# LitosConnector.net
KiCad netlist of a schematic drawn in Altium Designer
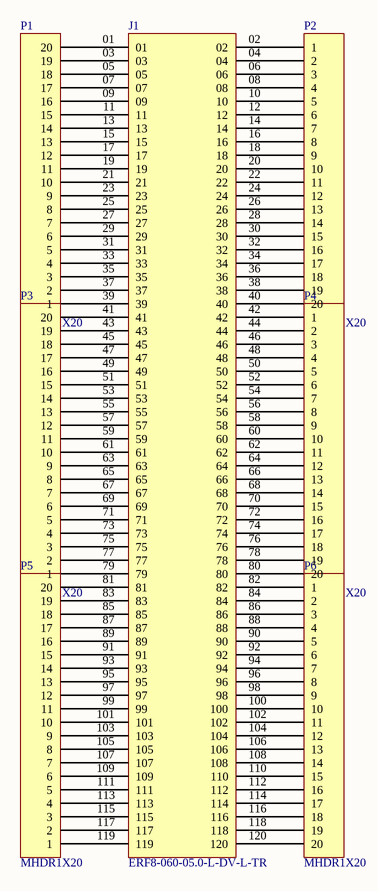
[diagram p0: LitosConnector.SchDoc]

(export (version "E")
  (design (tool "Eeschema 10.0.6"))
  (components
    (comp (ref "J1")
      (value "ERF8-060-05.0-L-DV-L-TR")
      (footprint "SAMTEC_ERF8-060-05.0-L-DV-L-TR")
      (libsource (lib "ERF8-060-05.0-L-DV-L-TR") (part "ERF8-060-05.0-L-DV-L-TR"))
    )
    (comp (ref "P1")
      (value "MHDR1X20")
      (footprint "MHDR1X20")
      (description "Header, 20-Pin")
      (fields (field (name "PUBLISHER") "Altium Limited"))
      (libsource (lib "") (part "MHDR1X20_1"))
    )
    (comp (ref "P2")
      (value "MHDR1X20")
      (footprint "MHDR1X20")
      (description "Header, 20-Pin")
      (fields (field (name "PUBLISHER") "Altium Limited"))
      (libsource (lib "Miscellaneous Connectors") (part "MHDR1X20"))
    )
    (comp (ref "P3")
      (value "MHDR1X20")
      (footprint "MHDR1X20")
      (description "Header, 20-Pin")
      (fields (field (name "PUBLISHER") "Altium Limited"))
      (libsource (lib "") (part "MHDR1X20_1"))
    )
    (comp (ref "P4")
      (value "MHDR1X20")
      (footprint "MHDR1X20")
      (description "Header, 20-Pin")
      (fields (field (name "PUBLISHER") "Altium Limited"))
      (libsource (lib "Miscellaneous Connectors") (part "MHDR1X20"))
    )
    (comp (ref "P5")
      (value "MHDR1X20")
      (footprint "MHDR1X20")
      (description "Header, 20-Pin")
      (fields (field (name "PUBLISHER") "Altium Limited"))
      (libsource (lib "") (part "MHDR1X20_1"))
    )
    (comp (ref "P6")
      (value "MHDR1X20")
      (footprint "MHDR1X20")
      (description "Header, 20-Pin")
      (fields (field (name "PUBLISHER") "Altium Limited"))
      (libsource (lib "Miscellaneous Connectors") (part "MHDR1X20"))
    )
  )
  (nets
    (net (code "1") (name "Net-(J1-Pad01)") (class "Default")
      (node (ref "J1") (pin "01") (pinfunction "01_01") (pintype "passive"))
      (node (ref "P1") (pin "20") (pinfunction "20_20") (pintype "passive"))
    )
    (net (code "2") (name "Net-(J1-Pad02)") (class "Default")
      (node (ref "J1") (pin "02") (pinfunction "02_02") (pintype "passive"))
      (node (ref "P2") (pin "1") (pinfunction "1_1") (pintype "passive"))
    )
    (net (code "3") (name "Net-(J1-Pad03)") (class "Default")
      (node (ref "J1") (pin "03") (pinfunction "03_03") (pintype "passive"))
      (node (ref "P1") (pin "19") (pinfunction "19_19") (pintype "passive"))
    )
    (net (code "4") (name "Net-(J1-Pad04)") (class "Default")
      (node (ref "J1") (pin "04") (pinfunction "04_04") (pintype "passive"))
      (node (ref "P2") (pin "2") (pinfunction "2_2") (pintype "passive"))
    )
    (net (code "5") (name "Net-(J1-Pad05)") (class "Default")
      (node (ref "J1") (pin "05") (pinfunction "05_05") (pintype "passive"))
      (node (ref "P1") (pin "18") (pinfunction "18_18") (pintype "passive"))
    )
    (net (code "6") (name "Net-(J1-Pad06)") (class "Default")
      (node (ref "J1") (pin "06") (pinfunction "06_06") (pintype "passive"))
      (node (ref "P2") (pin "3") (pinfunction "3_3") (pintype "passive"))
    )
    (net (code "7") (name "Net-(J1-Pad07)") (class "Default")
      (node (ref "J1") (pin "07") (pinfunction "07_07") (pintype "passive"))
      (node (ref "P1") (pin "17") (pinfunction "17_17") (pintype "passive"))
    )
    (net (code "8") (name "Net-(J1-Pad08)") (class "Default")
      (node (ref "J1") (pin "08") (pinfunction "08_08") (pintype "passive"))
      (node (ref "P2") (pin "4") (pinfunction "4_4") (pintype "passive"))
    )
    (net (code "9") (name "Net-(J1-Pad09)") (class "Default")
      (node (ref "J1") (pin "09") (pinfunction "09_09") (pintype "passive"))
      (node (ref "P1") (pin "16") (pinfunction "16_16") (pintype "passive"))
    )
    (net (code "10") (name "Net-(J1-Pad10)") (class "Default")
      (node (ref "J1") (pin "10") (pinfunction "10_10") (pintype "passive"))
      (node (ref "P2") (pin "5") (pinfunction "5_5") (pintype "passive"))
    )
    (net (code "11") (name "Net-(J1-Pad11)") (class "Default")
      (node (ref "J1") (pin "11") (pinfunction "11_11") (pintype "passive"))
      (node (ref "P1") (pin "15") (pinfunction "15_15") (pintype "passive"))
    )
    (net (code "12") (name "Net-(J1-Pad12)") (class "Default")
      (node (ref "J1") (pin "12") (pinfunction "12_12") (pintype "passive"))
      (node (ref "P2") (pin "6") (pinfunction "6_6") (pintype "passive"))
    )
    (net (code "13") (name "Net-(J1-Pad13)") (class "Default")
      (node (ref "J1") (pin "13") (pinfunction "13_13") (pintype "passive"))
      (node (ref "P1") (pin "14") (pinfunction "14_14") (pintype "passive"))
    )
    (net (code "14") (name "Net-(J1-Pad14)") (class "Default")
      (node (ref "J1") (pin "14") (pinfunction "14_14") (pintype "passive"))
      (node (ref "P2") (pin "7") (pinfunction "7_7") (pintype "passive"))
    )
    (net (code "15") (name "Net-(J1-Pad15)") (class "Default")
      (node (ref "J1") (pin "15") (pinfunction "15_15") (pintype "passive"))
      (node (ref "P1") (pin "13") (pinfunction "13_13") (pintype "passive"))
    )
    (net (code "16") (name "Net-(J1-Pad16)") (class "Default")
      (node (ref "J1") (pin "16") (pinfunction "16_16") (pintype "passive"))
      (node (ref "P2") (pin "8") (pinfunction "8_8") (pintype "passive"))
    )
    (net (code "17") (name "Net-(J1-Pad17)") (class "Default")
      (node (ref "J1") (pin "17") (pinfunction "17_17") (pintype "passive"))
      (node (ref "P1") (pin "12") (pinfunction "12_12") (pintype "passive"))
    )
    (net (code "18") (name "Net-(J1-Pad18)") (class "Default")
      (node (ref "J1") (pin "18") (pinfunction "18_18") (pintype "passive"))
      (node (ref "P2") (pin "9") (pinfunction "9_9") (pintype "passive"))
    )
    (net (code "19") (name "Net-(J1-Pad19)") (class "Default")
      (node (ref "J1") (pin "19") (pinfunction "19_19") (pintype "passive"))
      (node (ref "P1") (pin "11") (pinfunction "11_11") (pintype "passive"))
    )
    (net (code "20") (name "Net-(J1-Pad20)") (class "Default")
      (node (ref "J1") (pin "20") (pinfunction "20_20") (pintype "passive"))
      (node (ref "P2") (pin "10") (pinfunction "10_10") (pintype "passive"))
    )
    (net (code "21") (name "Net-(J1-Pad21)") (class "Default")
      (node (ref "J1") (pin "21") (pinfunction "21_21") (pintype "passive"))
      (node (ref "P1") (pin "10") (pinfunction "10_10") (pintype "passive"))
    )
    (net (code "22") (name "Net-(J1-Pad22)") (class "Default")
      (node (ref "J1") (pin "22") (pinfunction "22_22") (pintype "passive"))
      (node (ref "P2") (pin "11") (pinfunction "11_11") (pintype "passive"))
    )
    (net (code "23") (name "Net-(J1-Pad23)") (class "Default")
      (node (ref "J1") (pin "23") (pinfunction "23_23") (pintype "passive"))
      (node (ref "P1") (pin "9") (pinfunction "9_9") (pintype "passive"))
    )
    (net (code "24") (name "Net-(J1-Pad24)") (class "Default")
      (node (ref "J1") (pin "24") (pinfunction "24_24") (pintype "passive"))
      (node (ref "P2") (pin "12") (pinfunction "12_12") (pintype "passive"))
    )
    (net (code "25") (name "Net-(J1-Pad25)") (class "Default")
      (node (ref "J1") (pin "25") (pinfunction "25_25") (pintype "passive"))
      (node (ref "P1") (pin "8") (pinfunction "8_8") (pintype "passive"))
    )
    (net (code "26") (name "Net-(J1-Pad26)") (class "Default")
      (node (ref "J1") (pin "26") (pinfunction "26_26") (pintype "passive"))
      (node (ref "P2") (pin "13") (pinfunction "13_13") (pintype "passive"))
    )
    (net (code "27") (name "Net-(J1-Pad27)") (class "Default")
      (node (ref "J1") (pin "27") (pinfunction "27_27") (pintype "passive"))
      (node (ref "P1") (pin "7") (pinfunction "7_7") (pintype "passive"))
    )
    (net (code "28") (name "Net-(J1-Pad28)") (class "Default")
      (node (ref "J1") (pin "28") (pinfunction "28_28") (pintype "passive"))
      (node (ref "P2") (pin "14") (pinfunction "14_14") (pintype "passive"))
    )
    (net (code "29") (name "Net-(J1-Pad29)") (class "Default")
      (node (ref "J1") (pin "29") (pinfunction "29_29") (pintype "passive"))
      (node (ref "P1") (pin "6") (pinfunction "6_6") (pintype "passive"))
    )
    (net (code "30") (name "Net-(J1-Pad30)") (class "Default")
      (node (ref "J1") (pin "30") (pinfunction "30_30") (pintype "passive"))
      (node (ref "P2") (pin "15") (pinfunction "15_15") (pintype "passive"))
    )
    (net (code "31") (name "Net-(J1-Pad31)") (class "Default")
      (node (ref "J1") (pin "31") (pinfunction "31_31") (pintype "passive"))
      (node (ref "P1") (pin "5") (pinfunction "5_5") (pintype "passive"))
    )
    (net (code "32") (name "Net-(J1-Pad32)") (class "Default")
      (node (ref "J1") (pin "32") (pinfunction "32_32") (pintype "passive"))
      (node (ref "P2") (pin "16") (pinfunction "16_16") (pintype "passive"))
    )
    (net (code "33") (name "Net-(J1-Pad33)") (class "Default")
      (node (ref "J1") (pin "33") (pinfunction "33_33") (pintype "passive"))
      (node (ref "P1") (pin "4") (pinfunction "4_4") (pintype "passive"))
    )
    (net (code "34") (name "Net-(J1-Pad34)") (class "Default")
      (node (ref "J1") (pin "34") (pinfunction "34_34") (pintype "passive"))
      (node (ref "P2") (pin "17") (pinfunction "17_17") (pintype "passive"))
    )
    (net (code "35") (name "Net-(J1-Pad35)") (class "Default")
      (node (ref "J1") (pin "35") (pinfunction "35_35") (pintype "passive"))
      (node (ref "P1") (pin "3") (pinfunction "3_3") (pintype "passive"))
    )
    (net (code "36") (name "Net-(J1-Pad36)") (class "Default")
      (node (ref "J1") (pin "36") (pinfunction "36_36") (pintype "passive"))
      (node (ref "P2") (pin "18") (pinfunction "18_18") (pintype "passive"))
    )
    (net (code "37") (name "Net-(J1-Pad37)") (class "Default")
      (node (ref "J1") (pin "37") (pinfunction "37_37") (pintype "passive"))
      (node (ref "P1") (pin "2") (pinfunction "2_2") (pintype "passive"))
    )
    (net (code "38") (name "Net-(J1-Pad38)") (class "Default")
      (node (ref "J1") (pin "38") (pinfunction "38_38") (pintype "passive"))
      (node (ref "P2") (pin "19") (pinfunction "19_19") (pintype "passive"))
    )
    (net (code "39") (name "Net-(J1-Pad39)") (class "Default")
      (node (ref "J1") (pin "39") (pinfunction "39_39") (pintype "passive"))
      (node (ref "P1") (pin "1") (pinfunction "1_1") (pintype "passive"))
    )
    (net (code "40") (name "Net-(J1-Pad40)") (class "Default")
      (node (ref "J1") (pin "40") (pinfunction "40_40") (pintype "passive"))
      (node (ref "P2") (pin "20") (pinfunction "20_20") (pintype "passive"))
    )
    (net (code "41") (name "Net-(J1-Pad41)") (class "Default")
      (node (ref "J1") (pin "41") (pinfunction "41_41") (pintype "passive"))
      (node (ref "P3") (pin "20") (pinfunction "20_20") (pintype "passive"))
    )
    (net (code "42") (name "Net-(J1-Pad42)") (class "Default")
      (node (ref "J1") (pin "42") (pinfunction "42_42") (pintype "passive"))
      (node (ref "P4") (pin "1") (pinfunction "1_1") (pintype "passive"))
    )
    (net (code "43") (name "Net-(J1-Pad43)") (class "Default")
      (node (ref "J1") (pin "43") (pinfunction "43_43") (pintype "passive"))
      (node (ref "P3") (pin "19") (pinfunction "19_19") (pintype "passive"))
    )
    (net (code "44") (name "Net-(J1-Pad44)") (class "Default")
      (node (ref "J1") (pin "44") (pinfunction "44_44") (pintype "passive"))
      (node (ref "P4") (pin "2") (pinfunction "2_2") (pintype "passive"))
    )
    (net (code "45") (name "Net-(J1-Pad45)") (class "Default")
      (node (ref "J1") (pin "45") (pinfunction "45_45") (pintype "passive"))
      (node (ref "P3") (pin "18") (pinfunction "18_18") (pintype "passive"))
    )
    (net (code "46") (name "Net-(J1-Pad46)") (class "Default")
      (node (ref "J1") (pin "46") (pinfunction "46_46") (pintype "passive"))
      (node (ref "P4") (pin "3") (pinfunction "3_3") (pintype "passive"))
    )
    (net (code "47") (name "Net-(J1-Pad47)") (class "Default")
      (node (ref "J1") (pin "47") (pinfunction "47_47") (pintype "passive"))
      (node (ref "P3") (pin "17") (pinfunction "17_17") (pintype "passive"))
    )
    (net (code "48") (name "Net-(J1-Pad48)") (class "Default")
      (node (ref "J1") (pin "48") (pinfunction "48_48") (pintype "passive"))
      (node (ref "P4") (pin "4") (pinfunction "4_4") (pintype "passive"))
    )
    (net (code "49") (name "Net-(J1-Pad49)") (class "Default")
      (node (ref "J1") (pin "49") (pinfunction "49_49") (pintype "passive"))
      (node (ref "P3") (pin "16") (pinfunction "16_16") (pintype "passive"))
    )
    (net (code "50") (name "Net-(J1-Pad50)") (class "Default")
      (node (ref "J1") (pin "50") (pinfunction "50_50") (pintype "passive"))
      (node (ref "P4") (pin "5") (pinfunction "5_5") (pintype "passive"))
    )
    (net (code "51") (name "Net-(J1-Pad51)") (class "Default")
      (node (ref "J1") (pin "51") (pinfunction "51_51") (pintype "passive"))
      (node (ref "P3") (pin "15") (pinfunction "15_15") (pintype "passive"))
    )
    (net (code "52") (name "Net-(J1-Pad52)") (class "Default")
      (node (ref "J1") (pin "52") (pinfunction "52_52") (pintype "passive"))
      (node (ref "P4") (pin "6") (pinfunction "6_6") (pintype "passive"))
    )
    (net (code "53") (name "Net-(J1-Pad53)") (class "Default")
      (node (ref "J1") (pin "53") (pinfunction "53_53") (pintype "passive"))
      (node (ref "P3") (pin "14") (pinfunction "14_14") (pintype "passive"))
    )
    (net (code "54") (name "Net-(J1-Pad54)") (class "Default")
      (node (ref "J1") (pin "54") (pinfunction "54_54") (pintype "passive"))
      (node (ref "P4") (pin "7") (pinfunction "7_7") (pintype "passive"))
    )
    (net (code "55") (name "Net-(J1-Pad55)") (class "Default")
      (node (ref "J1") (pin "55") (pinfunction "55_55") (pintype "passive"))
      (node (ref "P3") (pin "13") (pinfunction "13_13") (pintype "passive"))
    )
    (net (code "56") (name "Net-(J1-Pad56)") (class "Default")
      (node (ref "J1") (pin "56") (pinfunction "56_56") (pintype "passive"))
      (node (ref "P4") (pin "8") (pinfunction "8_8") (pintype "passive"))
    )
    (net (code "57") (name "Net-(J1-Pad57)") (class "Default")
      (node (ref "J1") (pin "57") (pinfunction "57_57") (pintype "passive"))
      (node (ref "P3") (pin "12") (pinfunction "12_12") (pintype "passive"))
    )
    (net (code "58") (name "Net-(J1-Pad58)") (class "Default")
      (node (ref "J1") (pin "58") (pinfunction "58_58") (pintype "passive"))
      (node (ref "P4") (pin "9") (pinfunction "9_9") (pintype "passive"))
    )
    (net (code "59") (name "Net-(J1-Pad59)") (class "Default")
      (node (ref "J1") (pin "59") (pinfunction "59_59") (pintype "passive"))
      (node (ref "P3") (pin "11") (pinfunction "11_11") (pintype "passive"))
    )
    (net (code "60") (name "Net-(J1-Pad60)") (class "Default")
      (node (ref "J1") (pin "60") (pinfunction "60_60") (pintype "passive"))
      (node (ref "P4") (pin "10") (pinfunction "10_10") (pintype "passive"))
    )
    (net (code "61") (name "Net-(J1-Pad61)") (class "Default")
      (node (ref "J1") (pin "61") (pinfunction "61_61") (pintype "passive"))
      (node (ref "P3") (pin "10") (pinfunction "10_10") (pintype "passive"))
    )
    (net (code "62") (name "Net-(J1-Pad62)") (class "Default")
      (node (ref "J1") (pin "62") (pinfunction "62_62") (pintype "passive"))
      (node (ref "P4") (pin "11") (pinfunction "11_11") (pintype "passive"))
    )
    (net (code "63") (name "Net-(J1-Pad63)") (class "Default")
      (node (ref "J1") (pin "63") (pinfunction "63_63") (pintype "passive"))
      (node (ref "P3") (pin "9") (pinfunction "9_9") (pintype "passive"))
    )
    (net (code "64") (name "Net-(J1-Pad64)") (class "Default")
      (node (ref "J1") (pin "64") (pinfunction "64_64") (pintype "passive"))
      (node (ref "P4") (pin "12") (pinfunction "12_12") (pintype "passive"))
    )
    (net (code "65") (name "Net-(J1-Pad65)") (class "Default")
      (node (ref "J1") (pin "65") (pinfunction "65_65") (pintype "passive"))
      (node (ref "P3") (pin "8") (pinfunction "8_8") (pintype "passive"))
    )
    (net (code "66") (name "Net-(J1-Pad66)") (class "Default")
      (node (ref "J1") (pin "66") (pinfunction "66_66") (pintype "passive"))
      (node (ref "P4") (pin "13") (pinfunction "13_13") (pintype "passive"))
    )
    (net (code "67") (name "Net-(J1-Pad67)") (class "Default")
      (node (ref "J1") (pin "67") (pinfunction "67_67") (pintype "passive"))
      (node (ref "P3") (pin "7") (pinfunction "7_7") (pintype "passive"))
    )
    (net (code "68") (name "Net-(J1-Pad68)") (class "Default")
      (node (ref "J1") (pin "68") (pinfunction "68_68") (pintype "passive"))
      (node (ref "P4") (pin "14") (pinfunction "14_14") (pintype "passive"))
    )
    (net (code "69") (name "Net-(J1-Pad69)") (class "Default")
      (node (ref "J1") (pin "69") (pinfunction "69_69") (pintype "passive"))
      (node (ref "P3") (pin "6") (pinfunction "6_6") (pintype "passive"))
    )
    (net (code "70") (name "Net-(J1-Pad70)") (class "Default")
      (node (ref "J1") (pin "70") (pinfunction "70_70") (pintype "passive"))
      (node (ref "P4") (pin "15") (pinfunction "15_15") (pintype "passive"))
    )
    (net (code "71") (name "Net-(J1-Pad71)") (class "Default")
      (node (ref "J1") (pin "71") (pinfunction "71_71") (pintype "passive"))
      (node (ref "P3") (pin "5") (pinfunction "5_5") (pintype "passive"))
    )
    (net (code "72") (name "Net-(J1-Pad72)") (class "Default")
      (node (ref "J1") (pin "72") (pinfunction "72_72") (pintype "passive"))
      (node (ref "P4") (pin "16") (pinfunction "16_16") (pintype "passive"))
    )
    (net (code "73") (name "Net-(J1-Pad73)") (class "Default")
      (node (ref "J1") (pin "73") (pinfunction "73_73") (pintype "passive"))
      (node (ref "P3") (pin "4") (pinfunction "4_4") (pintype "passive"))
    )
    (net (code "74") (name "Net-(J1-Pad74)") (class "Default")
      (node (ref "J1") (pin "74") (pinfunction "74_74") (pintype "passive"))
      (node (ref "P4") (pin "17") (pinfunction "17_17") (pintype "passive"))
    )
    (net (code "75") (name "Net-(J1-Pad75)") (class "Default")
      (node (ref "J1") (pin "75") (pinfunction "75_75") (pintype "passive"))
      (node (ref "P3") (pin "3") (pinfunction "3_3") (pintype "passive"))
    )
    (net (code "76") (name "Net-(J1-Pad76)") (class "Default")
      (node (ref "J1") (pin "76") (pinfunction "76_76") (pintype "passive"))
      (node (ref "P4") (pin "18") (pinfunction "18_18") (pintype "passive"))
    )
    (net (code "77") (name "Net-(J1-Pad77)") (class "Default")
      (node (ref "J1") (pin "77") (pinfunction "77_77") (pintype "passive"))
      (node (ref "P3") (pin "2") (pinfunction "2_2") (pintype "passive"))
    )
    (net (code "78") (name "Net-(J1-Pad78)") (class "Default")
      (node (ref "J1") (pin "78") (pinfunction "78_78") (pintype "passive"))
      (node (ref "P4") (pin "19") (pinfunction "19_19") (pintype "passive"))
    )
    (net (code "79") (name "Net-(J1-Pad79)") (class "Default")
      (node (ref "J1") (pin "79") (pinfunction "79_79") (pintype "passive"))
      (node (ref "P3") (pin "1") (pinfunction "1_1") (pintype "passive"))
    )
    (net (code "80") (name "Net-(J1-Pad80)") (class "Default")
      (node (ref "J1") (pin "80") (pinfunction "80_80") (pintype "passive"))
      (node (ref "P4") (pin "20") (pinfunction "20_20") (pintype "passive"))
    )
    (net (code "81") (name "Net-(J1-Pad81)") (class "Default")
      (node (ref "J1") (pin "81") (pinfunction "81_81") (pintype "passive"))
      (node (ref "P5") (pin "20") (pinfunction "20_20") (pintype "passive"))
    )
    (net (code "82") (name "Net-(J1-Pad82)") (class "Default")
      (node (ref "J1") (pin "82") (pinfunction "82_82") (pintype "passive"))
      (node (ref "P6") (pin "1") (pinfunction "1_1") (pintype "passive"))
    )
    (net (code "83") (name "Net-(J1-Pad83)") (class "Default")
      (node (ref "J1") (pin "83") (pinfunction "83_83") (pintype "passive"))
      (node (ref "P5") (pin "19") (pinfunction "19_19") (pintype "passive"))
    )
    (net (code "84") (name "Net-(J1-Pad84)") (class "Default")
      (node (ref "J1") (pin "84") (pinfunction "84_84") (pintype "passive"))
      (node (ref "P6") (pin "2") (pinfunction "2_2") (pintype "passive"))
    )
    (net (code "85") (name "Net-(J1-Pad85)") (class "Default")
      (node (ref "J1") (pin "85") (pinfunction "85_85") (pintype "passive"))
      (node (ref "P5") (pin "18") (pinfunction "18_18") (pintype "passive"))
    )
    (net (code "86") (name "Net-(J1-Pad86)") (class "Default")
      (node (ref "J1") (pin "86") (pinfunction "86_86") (pintype "passive"))
      (node (ref "P6") (pin "3") (pinfunction "3_3") (pintype "passive"))
    )
    (net (code "87") (name "Net-(J1-Pad87)") (class "Default")
      (node (ref "J1") (pin "87") (pinfunction "87_87") (pintype "passive"))
      (node (ref "P5") (pin "17") (pinfunction "17_17") (pintype "passive"))
    )
    (net (code "88") (name "Net-(J1-Pad88)") (class "Default")
      (node (ref "J1") (pin "88") (pinfunction "88_88") (pintype "passive"))
      (node (ref "P6") (pin "4") (pinfunction "4_4") (pintype "passive"))
    )
    (net (code "89") (name "Net-(J1-Pad89)") (class "Default")
      (node (ref "J1") (pin "89") (pinfunction "89_89") (pintype "passive"))
      (node (ref "P5") (pin "16") (pinfunction "16_16") (pintype "passive"))
    )
    (net (code "90") (name "Net-(J1-Pad90)") (class "Default")
      (node (ref "J1") (pin "90") (pinfunction "90_90") (pintype "passive"))
      (node (ref "P6") (pin "5") (pinfunction "5_5") (pintype "passive"))
    )
    (net (code "91") (name "Net-(J1-Pad91)") (class "Default")
      (node (ref "J1") (pin "91") (pinfunction "91_91") (pintype "passive"))
      (node (ref "P5") (pin "15") (pinfunction "15_15") (pintype "passive"))
    )
    (net (code "92") (name "Net-(J1-Pad92)") (class "Default")
      (node (ref "J1") (pin "92") (pinfunction "92_92") (pintype "passive"))
      (node (ref "P6") (pin "6") (pinfunction "6_6") (pintype "passive"))
    )
    (net (code "93") (name "Net-(J1-Pad93)") (class "Default")
      (node (ref "J1") (pin "93") (pinfunction "93_93") (pintype "passive"))
      (node (ref "P5") (pin "14") (pinfunction "14_14") (pintype "passive"))
    )
    (net (code "94") (name "Net-(J1-Pad94)") (class "Default")
      (node (ref "J1") (pin "94") (pinfunction "94_94") (pintype "passive"))
      (node (ref "P6") (pin "7") (pinfunction "7_7") (pintype "passive"))
    )
    (net (code "95") (name "Net-(J1-Pad95)") (class "Default")
      (node (ref "J1") (pin "95") (pinfunction "95_95") (pintype "passive"))
      (node (ref "P5") (pin "13") (pinfunction "13_13") (pintype "passive"))
    )
    (net (code "96") (name "Net-(J1-Pad96)") (class "Default")
      (node (ref "J1") (pin "96") (pinfunction "96_96") (pintype "passive"))
      (node (ref "P6") (pin "8") (pinfunction "8_8") (pintype "passive"))
    )
    (net (code "97") (name "Net-(J1-Pad97)") (class "Default")
      (node (ref "J1") (pin "97") (pinfunction "97_97") (pintype "passive"))
      (node (ref "P5") (pin "12") (pinfunction "12_12") (pintype "passive"))
    )
    (net (code "98") (name "Net-(J1-Pad98)") (class "Default")
      (node (ref "J1") (pin "98") (pinfunction "98_98") (pintype "passive"))
      (node (ref "P6") (pin "9") (pinfunction "9_9") (pintype "passive"))
    )
    (net (code "99") (name "Net-(J1-Pad99)") (class "Default")
      (node (ref "J1") (pin "99") (pinfunction "99_99") (pintype "passive"))
      (node (ref "P5") (pin "11") (pinfunction "11_11") (pintype "passive"))
    )
    (net (code "100") (name "Net-(J1-Pad100)") (class "Default")
      (node (ref "J1") (pin "100") (pinfunction "100_100") (pintype "passive"))
      (node (ref "P6") (pin "10") (pinfunction "10_10") (pintype "passive"))
    )
    (net (code "101") (name "Net-(J1-Pad101)") (class "Default")
      (node (ref "J1") (pin "101") (pinfunction "101_101") (pintype "passive"))
      (node (ref "P5") (pin "10") (pinfunction "10_10") (pintype "passive"))
    )
    (net (code "102") (name "Net-(J1-Pad102)") (class "Default")
      (node (ref "J1") (pin "102") (pinfunction "102_102") (pintype "passive"))
      (node (ref "P6") (pin "11") (pinfunction "11_11") (pintype "passive"))
    )
    (net (code "103") (name "Net-(J1-Pad103)") (class "Default")
      (node (ref "J1") (pin "103") (pinfunction "103_103") (pintype "passive"))
      (node (ref "P5") (pin "9") (pinfunction "9_9") (pintype "passive"))
    )
    (net (code "104") (name "Net-(J1-Pad104)") (class "Default")
      (node (ref "J1") (pin "104") (pinfunction "104_104") (pintype "passive"))
      (node (ref "P6") (pin "12") (pinfunction "12_12") (pintype "passive"))
    )
    (net (code "105") (name "Net-(J1-Pad105)") (class "Default")
      (node (ref "J1") (pin "105") (pinfunction "105_105") (pintype "passive"))
      (node (ref "P5") (pin "8") (pinfunction "8_8") (pintype "passive"))
    )
    (net (code "106") (name "Net-(J1-Pad106)") (class "Default")
      (node (ref "J1") (pin "106") (pinfunction "106_106") (pintype "passive"))
      (node (ref "P6") (pin "13") (pinfunction "13_13") (pintype "passive"))
    )
    (net (code "107") (name "Net-(J1-Pad107)") (class "Default")
      (node (ref "J1") (pin "107") (pinfunction "107_107") (pintype "passive"))
      (node (ref "P5") (pin "7") (pinfunction "7_7") (pintype "passive"))
    )
    (net (code "108") (name "Net-(J1-Pad108)") (class "Default")
      (node (ref "J1") (pin "108") (pinfunction "108_108") (pintype "passive"))
      (node (ref "P6") (pin "14") (pinfunction "14_14") (pintype "passive"))
    )
    (net (code "109") (name "Net-(J1-Pad109)") (class "Default")
      (node (ref "J1") (pin "109") (pinfunction "109_109") (pintype "passive"))
      (node (ref "P5") (pin "6") (pinfunction "6_6") (pintype "passive"))
    )
    (net (code "110") (name "Net-(J1-Pad110)") (class "Default")
      (node (ref "J1") (pin "110") (pinfunction "110_110") (pintype "passive"))
      (node (ref "P6") (pin "15") (pinfunction "15_15") (pintype "passive"))
    )
    (net (code "111") (name "Net-(J1-Pad111)") (class "Default")
      (node (ref "J1") (pin "111") (pinfunction "111_111") (pintype "passive"))
      (node (ref "P5") (pin "5") (pinfunction "5_5") (pintype "passive"))
    )
    (net (code "112") (name "Net-(J1-Pad112)") (class "Default")
      (node (ref "J1") (pin "112") (pinfunction "112_112") (pintype "passive"))
      (node (ref "P6") (pin "16") (pinfunction "16_16") (pintype "passive"))
    )
    (net (code "113") (name "Net-(J1-Pad113)") (class "Default")
      (node (ref "J1") (pin "113") (pinfunction "113_113") (pintype "passive"))
      (node (ref "P5") (pin "4") (pinfunction "4_4") (pintype "passive"))
    )
    (net (code "114") (name "Net-(J1-Pad114)") (class "Default")
      (node (ref "J1") (pin "114") (pinfunction "114_114") (pintype "passive"))
      (node (ref "P6") (pin "17") (pinfunction "17_17") (pintype "passive"))
    )
    (net (code "115") (name "Net-(J1-Pad115)") (class "Default")
      (node (ref "J1") (pin "115") (pinfunction "115_115") (pintype "passive"))
      (node (ref "P5") (pin "3") (pinfunction "3_3") (pintype "passive"))
    )
    (net (code "116") (name "Net-(J1-Pad116)") (class "Default")
      (node (ref "J1") (pin "116") (pinfunction "116_116") (pintype "passive"))
      (node (ref "P6") (pin "18") (pinfunction "18_18") (pintype "passive"))
    )
    (net (code "117") (name "Net-(J1-Pad117)") (class "Default")
      (node (ref "J1") (pin "117") (pinfunction "117_117") (pintype "passive"))
      (node (ref "P5") (pin "2") (pinfunction "2_2") (pintype "passive"))
    )
    (net (code "118") (name "Net-(J1-Pad118)") (class "Default")
      (node (ref "J1") (pin "118") (pinfunction "118_118") (pintype "passive"))
      (node (ref "P6") (pin "19") (pinfunction "19_19") (pintype "passive"))
    )
    (net (code "119") (name "Net-(J1-Pad119)") (class "Default")
      (node (ref "J1") (pin "119") (pinfunction "119_119") (pintype "passive"))
      (node (ref "P5") (pin "1") (pinfunction "1_1") (pintype "passive"))
    )
    (net (code "120") (name "Net-(J1-Pad120)") (class "Default")
      (node (ref "J1") (pin "120") (pinfunction "120_120") (pintype "passive"))
      (node (ref "P6") (pin "20") (pinfunction "20_20") (pintype "passive"))
    )
  )
)
